# Front_Node_MiniLock.net
KiCad netlist of a schematic drawn in EAGLE
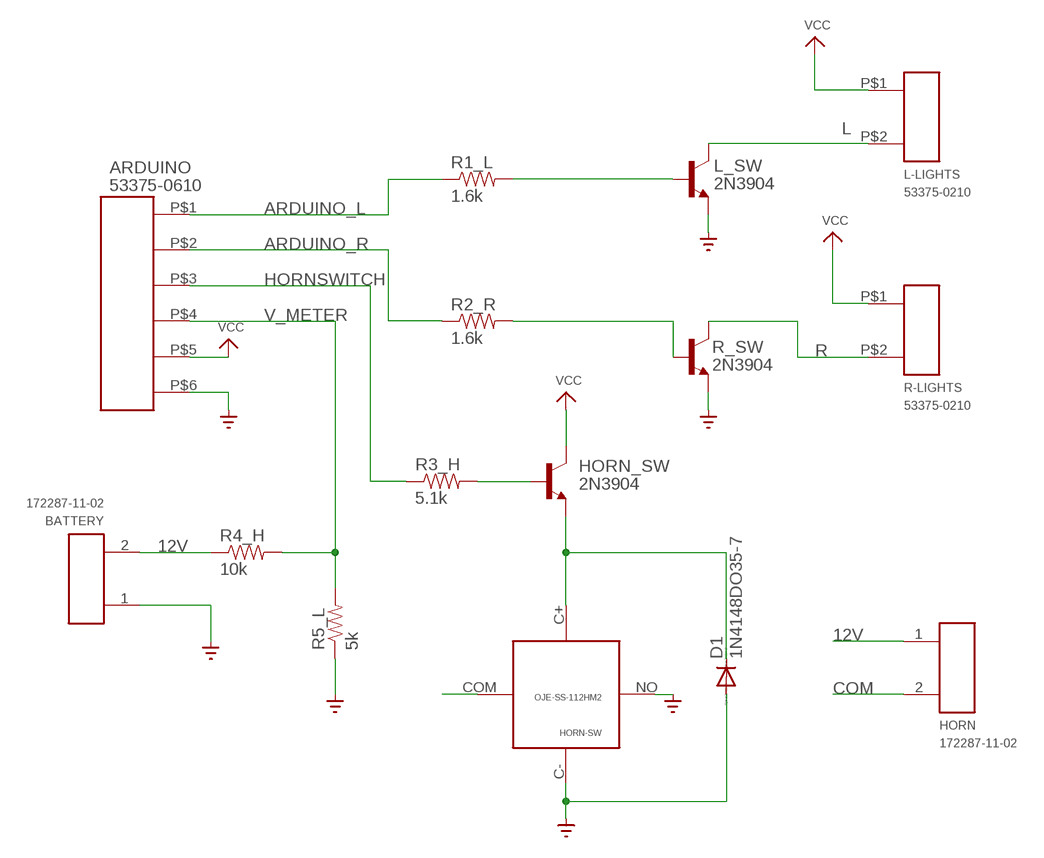
[diagram p0: schematic, sheet 1]

(export (version "E")
  (design (tool "Eeschema 10.0.6"))
  (components
    (comp (ref "ARDUINO")
      (value "53375-0610")
      (footprint "eagle-import:53375-0610-MINI-LOCK")
      (libsource (lib "eagle-import") (part "53375-0610"))
    )
    (comp (ref "BATTERY")
      (value "172287-11-02")
      (footprint "eagle-import:172287-ULTRA-FIT")
      (libsource (lib "eagle-import") (part "172287-11-02"))
    )
    (comp (ref "D1")
      (value "1N4148DO35-7")
      (footprint "eagle-import:DO35-7")
      (libsource (lib "eagle-import") (part "1N4148DO35-7"))
    )
    (comp (ref "HORN")
      (value "172287-11-02")
      (footprint "eagle-import:172287-ULTRA-FIT")
      (libsource (lib "eagle-import") (part "172287-11-02"))
    )
    (comp (ref "HORN-SW")
      (value "OJE-SS-112HM2")
      (footprint "eagle-import:OJE-SS-112HM2-SPST-RELAY")
      (libsource (lib "eagle-import") (part "OJE-SS-112HM2"))
    )
    (comp (ref "HORN_SW")
      (value "2N3904")
      (footprint "eagle-import:TO92")
      (libsource (lib "eagle-import") (part "2N3904"))
    )
    (comp (ref "L-LIGHTS")
      (value "53375-0210")
      (footprint "eagle-import:53375-0210-MINI-LOCK")
      (libsource (lib "eagle-import") (part "53375-0210"))
    )
    (comp (ref "L_SW")
      (value "2N3904")
      (footprint "eagle-import:TO92")
      (libsource (lib "eagle-import") (part "2N3904"))
    )
    (comp (ref "R-LIGHTS")
      (value "53375-0210")
      (footprint "eagle-import:53375-0210-MINI-LOCK")
      (libsource (lib "eagle-import") (part "53375-0210"))
    )
    (comp (ref "R1_L")
      (value "1.6k")
      (footprint "eagle-import:1_6W-RES")
      (libsource (lib "eagle-import") (part "RESISTORPTH-1/6W"))
    )
    (comp (ref "R2_R")
      (value "1.6k")
      (footprint "eagle-import:1_6W-RES")
      (libsource (lib "eagle-import") (part "RESISTORPTH-1/6W"))
    )
    (comp (ref "R3_H")
      (value "5.1k")
      (footprint "eagle-import:1_6W-RES")
      (libsource (lib "eagle-import") (part "RESISTORPTH-1/6W"))
    )
    (comp (ref "R4_H")
      (value "10k")
      (footprint "eagle-import:1_6W-RES")
      (libsource (lib "eagle-import") (part "RESISTORPTH-1/6W"))
    )
    (comp (ref "R5_L")
      (value "5k")
      (footprint "eagle-import:1_6W-RES")
      (libsource (lib "eagle-import") (part "RESISTORPTH-1/6W"))
    )
    (comp (ref "R_SW")
      (value "2N3904")
      (footprint "eagle-import:TO92")
      (libsource (lib "eagle-import") (part "2N3904"))
    )
  )
  (nets
    (net (code "1") (name "/12V") (class "Default")
      (node (ref "BATTERY") (pin "2") (pinfunction "2_2") (pintype "bidirectional"))
      (node (ref "HORN") (pin "1") (pinfunction "1_1") (pintype "bidirectional"))
      (node (ref "R4_H") (pin "1") (pinfunction "1_1") (pintype "passive"))
    )
    (net (code "2") (name "/ARDUINO_L") (class "Default")
      (node (ref "ARDUINO") (pin "P$1") (pinfunction "P$1_P$1") (pintype "bidirectional"))
      (node (ref "R1_L") (pin "1") (pinfunction "1_1") (pintype "passive"))
    )
    (net (code "3") (name "/ARDUINO_R") (class "Default")
      (node (ref "ARDUINO") (pin "P$2") (pinfunction "P$2_P$2") (pintype "bidirectional"))
      (node (ref "R2_R") (pin "1") (pinfunction "1_1") (pintype "passive"))
    )
    (net (code "4") (name "/COM") (class "Default")
      (node (ref "HORN") (pin "2") (pinfunction "2_2") (pintype "bidirectional"))
      (node (ref "HORN-SW") (pin "COM") (pinfunction "COM_COM") (pintype "bidirectional"))
    )
    (net (code "5") (name "/HORNSWITCH") (class "Default")
      (node (ref "ARDUINO") (pin "P$3") (pinfunction "P$3_P$3") (pintype "bidirectional"))
      (node (ref "R3_H") (pin "1") (pinfunction "1_1") (pintype "passive"))
    )
    (net (code "6") (name "/L") (class "Default")
      (node (ref "L-LIGHTS") (pin "P$2") (pinfunction "2_P$2") (pintype "bidirectional"))
      (node (ref "L_SW") (pin "1") (pinfunction "C_1") (pintype "passive"))
    )
    (net (code "7") (name "/R") (class "Default")
      (node (ref "R-LIGHTS") (pin "P$2") (pinfunction "2_P$2") (pintype "bidirectional"))
      (node (ref "R_SW") (pin "1") (pinfunction "C_1") (pintype "passive"))
    )
    (net (code "8") (name "/V_METER") (class "Default")
      (node (ref "ARDUINO") (pin "P$4") (pinfunction "P$4_P$4") (pintype "bidirectional"))
      (node (ref "R4_H") (pin "2") (pinfunction "2_2") (pintype "passive"))
      (node (ref "R5_L") (pin "2") (pinfunction "2_2") (pintype "passive"))
    )
    (net (code "9") (name "GND_") (class "Default")
      (node (ref "ARDUINO") (pin "P$6") (pinfunction "P$6_P$6") (pintype "bidirectional"))
      (node (ref "BATTERY") (pin "1") (pinfunction "1_1") (pintype "bidirectional"))
      (node (ref "D1") (pin "A") (pinfunction "A_A") (pintype "passive"))
      (node (ref "HORN-SW") (pin "C-") (pinfunction "C-_C-") (pintype "bidirectional"))
      (node (ref "HORN-SW") (pin "NO") (pinfunction "NO_NO") (pintype "bidirectional"))
      (node (ref "L_SW") (pin "3") (pinfunction "E_3") (pintype "passive"))
      (node (ref "R5_L") (pin "1") (pinfunction "1_1") (pintype "passive"))
      (node (ref "R_SW") (pin "3") (pinfunction "E_3") (pintype "passive"))
    )
    (net (code "10") (name "Net-(HORN_SW-B)") (class "Default")
      (node (ref "HORN_SW") (pin "2") (pinfunction "B_2") (pintype "passive"))
      (node (ref "R3_H") (pin "2") (pinfunction "2_2") (pintype "passive"))
    )
    (net (code "11") (name "Net-(HORN_SW-E)") (class "Default")
      (node (ref "D1") (pin "C") (pinfunction "C_C") (pintype "passive"))
      (node (ref "HORN-SW") (pin "C+") (pinfunction "C+_C+") (pintype "bidirectional"))
      (node (ref "HORN_SW") (pin "3") (pinfunction "E_3") (pintype "passive"))
    )
    (net (code "12") (name "Net-(L_SW-B)") (class "Default")
      (node (ref "L_SW") (pin "2") (pinfunction "B_2") (pintype "passive"))
      (node (ref "R1_L") (pin "2") (pinfunction "2_2") (pintype "passive"))
    )
    (net (code "13") (name "Net-(R_SW-B)") (class "Default")
      (node (ref "R2_R") (pin "2") (pinfunction "2_2") (pintype "passive"))
      (node (ref "R_SW") (pin "2") (pinfunction "B_2") (pintype "passive"))
    )
    (net (code "14") (name "VCC") (class "Default")
      (node (ref "ARDUINO") (pin "P$5") (pinfunction "P$5_P$5") (pintype "bidirectional"))
      (node (ref "HORN_SW") (pin "1") (pinfunction "C_1") (pintype "passive"))
      (node (ref "L-LIGHTS") (pin "P$1") (pinfunction "1_P$1") (pintype "bidirectional"))
      (node (ref "R-LIGHTS") (pin "P$1") (pinfunction "1_P$1") (pintype "bidirectional"))
    )
  )
)
